# logic.net
KiCad netlist of a schematic drawn in EAGLE
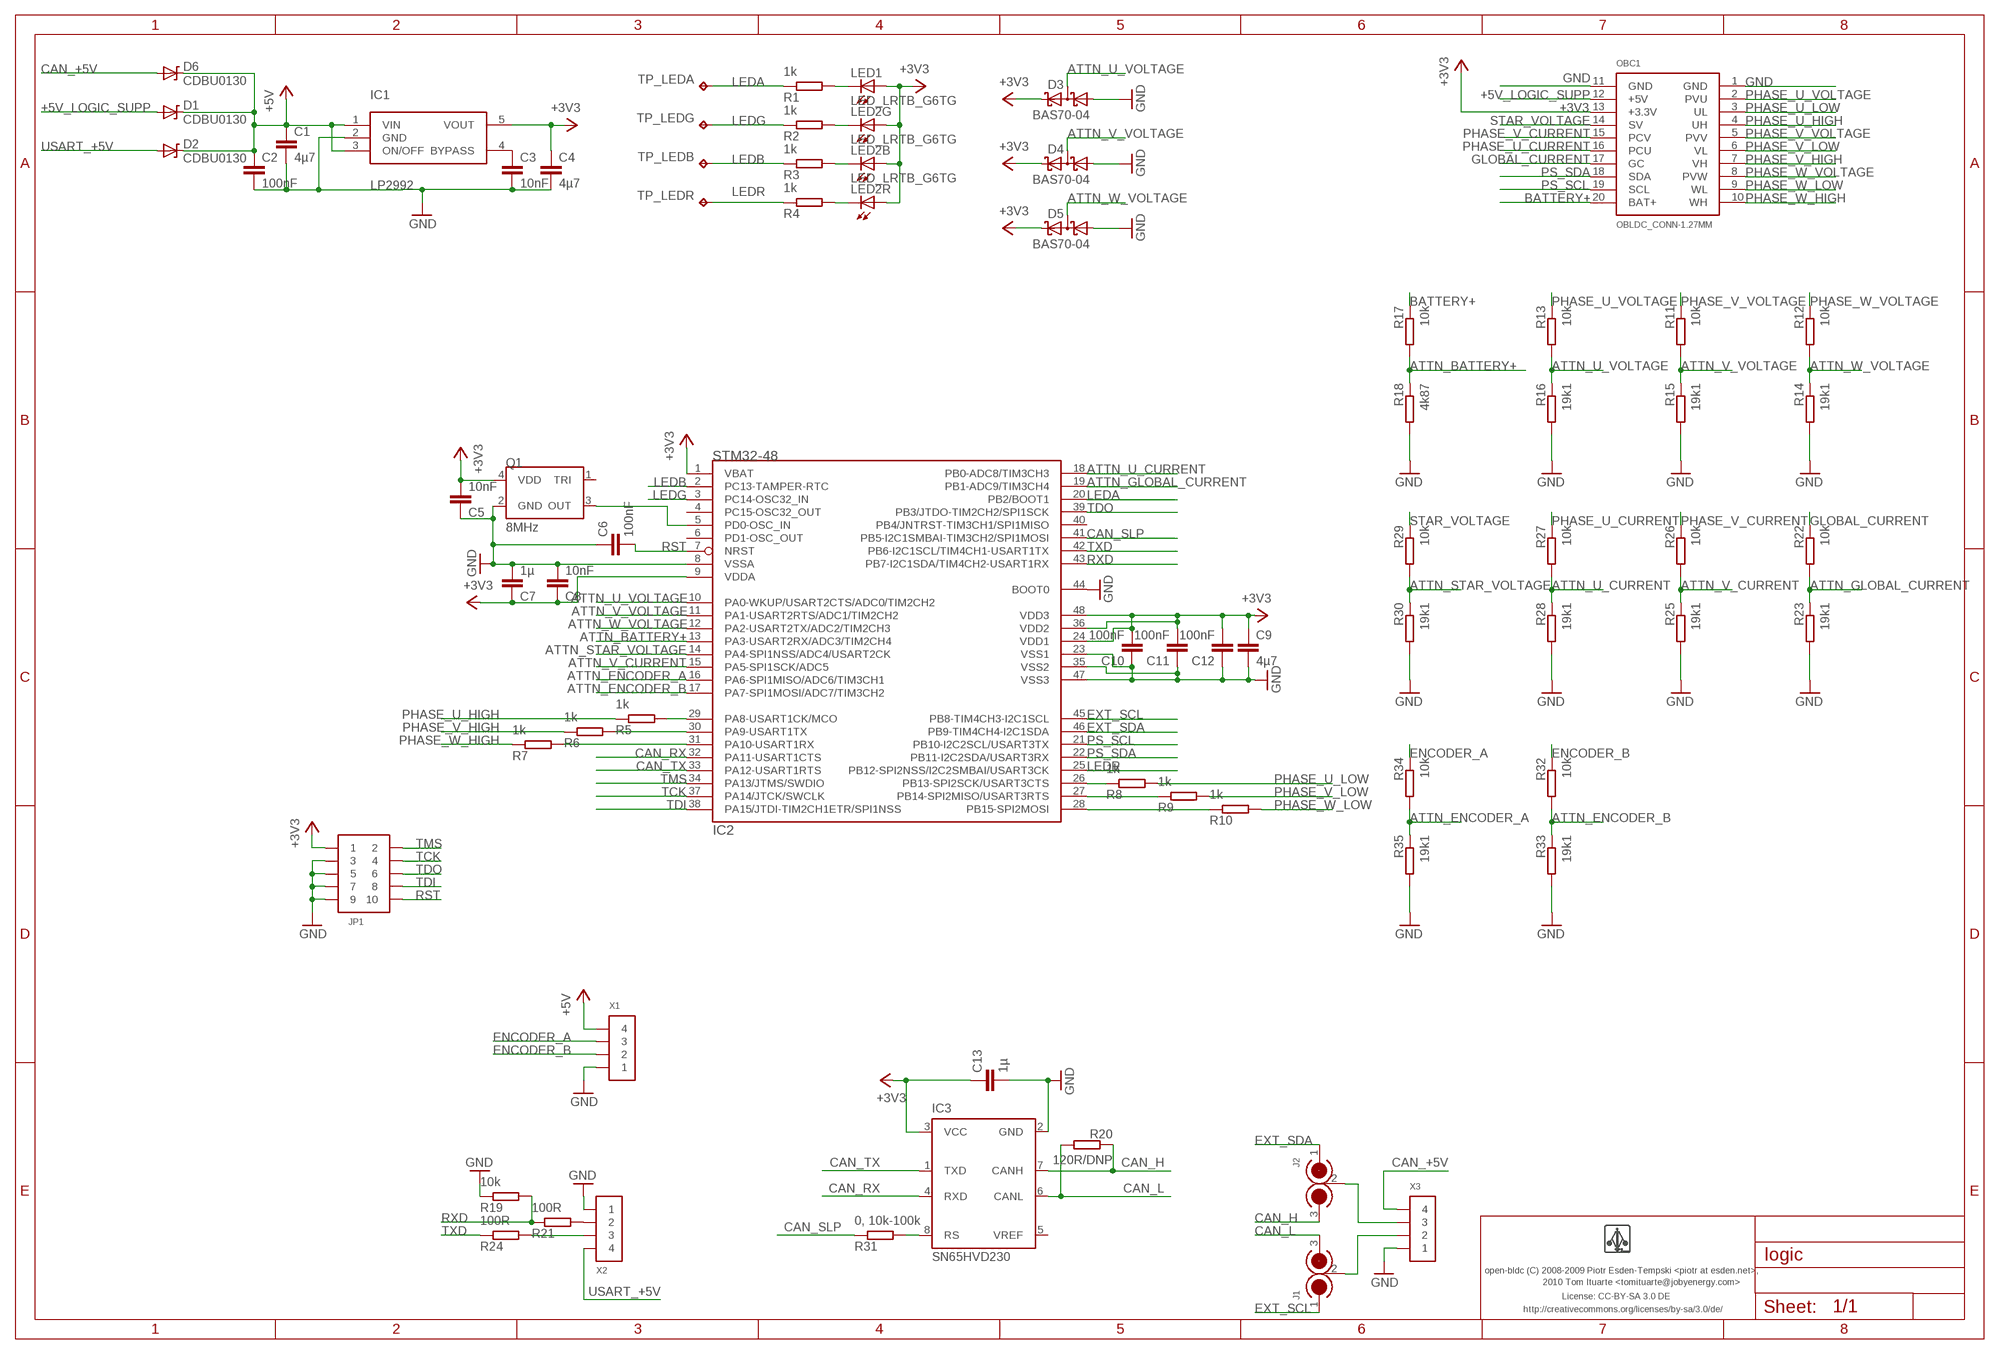
[diagram p0: schematic, sheet 1]

(export (version "E")
  (design (tool "Eeschema 10.0.6"))
  (components
    (comp (ref "C1")
      (value "4µ7")
      (footprint "eagle-import:0603-CAP")
      (libsource (lib "eagle-import") (part "CAPACITOR-0603"))
    )
    (comp (ref "C2")
      (value "100nF")
      (footprint "eagle-import:0603-CAP")
      (libsource (lib "eagle-import") (part "CAPACITOR-0603"))
    )
    (comp (ref "C3")
      (value "10nF")
      (footprint "eagle-import:0603-CAP")
      (libsource (lib "eagle-import") (part "CAPACITOR-0603"))
    )
    (comp (ref "C4")
      (value "4µ7")
      (footprint "eagle-import:0603-CAP")
      (libsource (lib "eagle-import") (part "CAPACITOR-0603"))
    )
    (comp (ref "C5")
      (value "10nF")
      (footprint "eagle-import:0603-CAP")
      (libsource (lib "eagle-import") (part "CAPACITOR-0603"))
    )
    (comp (ref "C6")
      (value "100nF")
      (footprint "eagle-import:0603-CAP")
      (libsource (lib "eagle-import") (part "CAPACITOR-0603"))
    )
    (comp (ref "C7")
      (value "1µ")
      (footprint "eagle-import:0603-CAP")
      (libsource (lib "eagle-import") (part "CAPACITOR-0603"))
    )
    (comp (ref "C8")
      (value "10nF")
      (footprint "eagle-import:0603-CAP")
      (libsource (lib "eagle-import") (part "CAPACITOR-0603"))
    )
    (comp (ref "C9")
      (value "4µ7")
      (footprint "eagle-import:0603-CAP")
      (libsource (lib "eagle-import") (part "CAPACITOR-0603"))
    )
    (comp (ref "C10")
      (value "100nF")
      (footprint "eagle-import:0603-CAP")
      (libsource (lib "eagle-import") (part "CAPACITOR-0603"))
    )
    (comp (ref "C11")
      (value "100nF")
      (footprint "eagle-import:0603-CAP")
      (libsource (lib "eagle-import") (part "CAPACITOR-0603"))
    )
    (comp (ref "C12")
      (value "100nF")
      (footprint "eagle-import:0603-CAP")
      (libsource (lib "eagle-import") (part "CAPACITOR-0603"))
    )
    (comp (ref "C13")
      (value "1µ")
      (footprint "eagle-import:0603-CAP")
      (libsource (lib "eagle-import") (part "CAPACITOR-0603"))
    )
    (comp (ref "D1")
      (value "CDBU0130")
      (footprint "eagle-import:0603-LED")
      (libsource (lib "eagle-import") (part "DIODE-ZENER-0603"))
    )
    (comp (ref "D2")
      (value "CDBU0130")
      (footprint "eagle-import:0603-LED")
      (libsource (lib "eagle-import") (part "DIODE-ZENER-0603"))
    )
    (comp (ref "D3")
      (value "BAS70-04")
      (footprint "eagle-import:SOT23")
      (libsource (lib "eagle-import") (part "BAS70-04"))
    )
    (comp (ref "D4")
      (value "BAS70-04")
      (footprint "eagle-import:SOT23")
      (libsource (lib "eagle-import") (part "BAS70-04"))
    )
    (comp (ref "D5")
      (value "BAS70-04")
      (footprint "eagle-import:SOT23")
      (libsource (lib "eagle-import") (part "BAS70-04"))
    )
    (comp (ref "D6")
      (value "CDBU0130")
      (footprint "eagle-import:0603-LED")
      (libsource (lib "eagle-import") (part "DIODE-ZENER-0603"))
    )
    (comp (ref "IC1")
      (value "LP2992")
      (footprint "eagle-import:SOT23-5")
      (libsource (lib "eagle-import") (part "LP2992"))
    )
    (comp (ref "IC2")
      (value "STM32-48")
      (footprint "eagle-import:LQFP48")
      (libsource (lib "eagle-import") (part "STM32-48"))
    )
    (comp (ref "IC3")
      (value "SN65HVD230")
      (footprint "eagle-import:SO8")
      (libsource (lib "eagle-import") (part "SN65HVD230"))
    )
    (comp (ref "J1")
      (value "CIRC_JMP_2")
      (footprint "eagle-import:CIRC_JMP_2")
      (libsource (lib "eagle-import") (part "CIRC_JMP_2"))
    )
    (comp (ref "J2")
      (value "CIRC_JMP_2")
      (footprint "eagle-import:CIRC_JMP_2")
      (libsource (lib "eagle-import") (part "CIRC_JMP_2"))
    )
    (comp (ref "JP1")
      (value "PIN_HDR_EDG_1.27MM_5-2-DH")
      (footprint "eagle-import:PIN_HDR_1.27MM_SMD_DH_10")
      (libsource (lib "eagle-import") (part "PIN_HDR_EDG_1.27MM_5-2-DH"))
    )
    (comp (ref "LED1")
      (value "AMBER")
      (footprint "eagle-import:0603-LED")
      (libsource (lib "eagle-import") (part "LED-0603"))
    )
    (comp (ref "LED2")
      (value "LED_LRTB_G6TG")
      (footprint "eagle-import:PLCC6")
      (libsource (lib "eagle-import") (part "LED_LRTB_G6TG"))
    )
    (comp (ref "OBC1")
      (value "OBLDC_CONN-1.27MM")
      (footprint "eagle-import:OBLDC_CONN")
      (libsource (lib "eagle-import") (part "OBLDC_CONN-1.27MM"))
    )
    (comp (ref "Q1")
      (value "8MHz")
      (footprint "eagle-import:ASE_OSCILLATOR")
      (libsource (lib "eagle-import") (part "ASE_ASCILLATOR"))
    )
    (comp (ref "R1")
      (value "1k")
      (footprint "eagle-import:0603-RES")
      (libsource (lib "eagle-import") (part "RESISTOR-0603"))
    )
    (comp (ref "R2")
      (value "1k")
      (footprint "eagle-import:0603-RES")
      (libsource (lib "eagle-import") (part "RESISTOR-0603"))
    )
    (comp (ref "R3")
      (value "1k")
      (footprint "eagle-import:0603-RES")
      (libsource (lib "eagle-import") (part "RESISTOR-0603"))
    )
    (comp (ref "R4")
      (value "1k")
      (footprint "eagle-import:0603-RES")
      (libsource (lib "eagle-import") (part "RESISTOR-0603"))
    )
    (comp (ref "R5")
      (value "1k")
      (footprint "eagle-import:0603-RES")
      (libsource (lib "eagle-import") (part "RESISTOR-0603"))
    )
    (comp (ref "R6")
      (value "1k")
      (footprint "eagle-import:0603-RES")
      (libsource (lib "eagle-import") (part "RESISTOR-0603"))
    )
    (comp (ref "R7")
      (value "1k")
      (footprint "eagle-import:0603-RES")
      (libsource (lib "eagle-import") (part "RESISTOR-0603"))
    )
    (comp (ref "R8")
      (value "1k")
      (footprint "eagle-import:0603-RES")
      (libsource (lib "eagle-import") (part "RESISTOR-0603"))
    )
    (comp (ref "R9")
      (value "1k")
      (footprint "eagle-import:0603-RES")
      (libsource (lib "eagle-import") (part "RESISTOR-0603"))
    )
    (comp (ref "R10")
      (value "1k")
      (footprint "eagle-import:0603-RES")
      (libsource (lib "eagle-import") (part "RESISTOR-0603"))
    )
    (comp (ref "R11")
      (value "10k")
      (footprint "eagle-import:0603-RES")
      (libsource (lib "eagle-import") (part "RESISTOR-0603"))
    )
    (comp (ref "R12")
      (value "10k")
      (footprint "eagle-import:0603-RES")
      (libsource (lib "eagle-import") (part "RESISTOR-0603"))
    )
    (comp (ref "R13")
      (value "10k")
      (footprint "eagle-import:0603-RES")
      (libsource (lib "eagle-import") (part "RESISTOR-0603"))
    )
    (comp (ref "R14")
      (value "19k1")
      (footprint "eagle-import:0603-RES")
      (libsource (lib "eagle-import") (part "RESISTOR-0603"))
    )
    (comp (ref "R15")
      (value "19k1")
      (footprint "eagle-import:0603-RES")
      (libsource (lib "eagle-import") (part "RESISTOR-0603"))
    )
    (comp (ref "R16")
      (value "19k1")
      (footprint "eagle-import:0603-RES")
      (libsource (lib "eagle-import") (part "RESISTOR-0603"))
    )
    (comp (ref "R17")
      (value "10k")
      (footprint "eagle-import:0603-RES")
      (libsource (lib "eagle-import") (part "RESISTOR-0603"))
    )
    (comp (ref "R18")
      (value "4k87")
      (footprint "eagle-import:0603-RES")
      (libsource (lib "eagle-import") (part "RESISTOR-0603"))
    )
    (comp (ref "R19")
      (value "10k")
      (footprint "eagle-import:0603-RES")
      (libsource (lib "eagle-import") (part "RESISTOR-0603"))
    )
    (comp (ref "R20")
      (value "120R/DNP")
      (footprint "eagle-import:0603-RES")
      (libsource (lib "eagle-import") (part "RESISTOR-0603"))
    )
    (comp (ref "R21")
      (value "100R")
      (footprint "eagle-import:0603-RES")
      (libsource (lib "eagle-import") (part "RESISTOR-0603"))
    )
    (comp (ref "R22")
      (value "10k")
      (footprint "eagle-import:0603-RES")
      (libsource (lib "eagle-import") (part "RESISTOR-0603"))
    )
    (comp (ref "R23")
      (value "19k1")
      (footprint "eagle-import:0603-RES")
      (libsource (lib "eagle-import") (part "RESISTOR-0603"))
    )
    (comp (ref "R24")
      (value "100R")
      (footprint "eagle-import:0603-RES")
      (libsource (lib "eagle-import") (part "RESISTOR-0603"))
    )
    (comp (ref "R25")
      (value "19k1")
      (footprint "eagle-import:0603-RES")
      (libsource (lib "eagle-import") (part "RESISTOR-0603"))
    )
    (comp (ref "R26")
      (value "10k")
      (footprint "eagle-import:0603-RES")
      (libsource (lib "eagle-import") (part "RESISTOR-0603"))
    )
    (comp (ref "R27")
      (value "10k")
      (footprint "eagle-import:0603-RES")
      (libsource (lib "eagle-import") (part "RESISTOR-0603"))
    )
    (comp (ref "R28")
      (value "19k1")
      (footprint "eagle-import:0603-RES")
      (libsource (lib "eagle-import") (part "RESISTOR-0603"))
    )
    (comp (ref "R29")
      (value "10k")
      (footprint "eagle-import:0603-RES")
      (libsource (lib "eagle-import") (part "RESISTOR-0603"))
    )
    (comp (ref "R30")
      (value "19k1")
      (footprint "eagle-import:0603-RES")
      (libsource (lib "eagle-import") (part "RESISTOR-0603"))
    )
    (comp (ref "R31")
      (value "0, 10k-100k")
      (footprint "eagle-import:0603-RES")
      (libsource (lib "eagle-import") (part "RESISTOR-0603"))
    )
    (comp (ref "R32")
      (value "10k")
      (footprint "eagle-import:0603-RES")
      (libsource (lib "eagle-import") (part "RESISTOR-0603"))
    )
    (comp (ref "R33")
      (value "19k1")
      (footprint "eagle-import:0603-RES")
      (libsource (lib "eagle-import") (part "RESISTOR-0603"))
    )
    (comp (ref "R34")
      (value "10k")
      (footprint "eagle-import:0603-RES")
      (libsource (lib "eagle-import") (part "RESISTOR-0603"))
    )
    (comp (ref "R35")
      (value "19k1")
      (footprint "eagle-import:0603-RES")
      (libsource (lib "eagle-import") (part "RESISTOR-0603"))
    )
    (comp (ref "TP_LEDA")
      (value "TP-SMD")
      (footprint "eagle-import:MINI_TESTPAD")
      (libsource (lib "eagle-import") (part "TP-SMD"))
    )
    (comp (ref "TP_LEDB")
      (value "TP-SMD")
      (footprint "eagle-import:MINI_TESTPAD")
      (libsource (lib "eagle-import") (part "TP-SMD"))
    )
    (comp (ref "TP_LEDG")
      (value "TP-SMD")
      (footprint "eagle-import:MINI_TESTPAD")
      (libsource (lib "eagle-import") (part "TP-SMD"))
    )
    (comp (ref "TP_LEDR")
      (value "TP-SMD")
      (footprint "eagle-import:MINI_TESTPAD")
      (libsource (lib "eagle-import") (part "TP-SMD"))
    )
    (comp (ref "U$1")
      (value "LOGO")
      (footprint "eagle-import:LOGO")
      (libsource (lib "eagle-import") (part "LOGO-NORM"))
    )
    (comp (ref "X1")
      (value "CONN_4-1-53261")
      (footprint "eagle-import:PB-53261-04")
      (libsource (lib "eagle-import") (part "CONN_4-1-53261"))
    )
    (comp (ref "X2")
      (value "CONN_4-1-53261")
      (footprint "eagle-import:PB-53261-04")
      (libsource (lib "eagle-import") (part "CONN_4-1-53261"))
    )
    (comp (ref "X3")
      (value "CONN_4-1-53261")
      (footprint "eagle-import:PB-53261-04")
      (libsource (lib "eagle-import") (part "CONN_4-1-53261"))
    )
  )
  (nets
    (net (code "1") (name "+3V3") (class "Default")
      (node (ref "C10") (pin "P$2") (pinfunction "2_P$2") (pintype "passive"))
      (node (ref "C11") (pin "P$2") (pinfunction "2_P$2") (pintype "passive"))
      (node (ref "C12") (pin "P$2") (pinfunction "2_P$2") (pintype "passive"))
      (node (ref "C13") (pin "P$1") (pinfunction "1_P$1") (pintype "passive"))
      (node (ref "C4") (pin "P$1") (pinfunction "1_P$1") (pintype "passive"))
      (node (ref "C5") (pin "P$2") (pinfunction "2_P$2") (pintype "passive"))
      (node (ref "C7") (pin "P$1") (pinfunction "1_P$1") (pintype "passive"))
      (node (ref "C8") (pin "P$1") (pinfunction "1_P$1") (pintype "passive"))
      (node (ref "C9") (pin "P$1") (pinfunction "1_P$1") (pintype "passive"))
      (node (ref "D3") (pin "2") (pinfunction "C2_2") (pintype "passive"))
      (node (ref "D4") (pin "2") (pinfunction "C2_2") (pintype "passive"))
      (node (ref "D5") (pin "2") (pinfunction "C2_2") (pintype "passive"))
      (node (ref "IC1") (pin "5") (pinfunction "VOUT_5") (pintype "bidirectional"))
      (node (ref "IC2") (pin "1") (pinfunction "VBAT_1") (pintype "power_in"))
      (node (ref "IC2") (pin "24") (pinfunction "VDD1_24") (pintype "power_in"))
      (node (ref "IC2") (pin "36") (pinfunction "VDD2_36") (pintype "power_in"))
      (node (ref "IC2") (pin "48") (pinfunction "VDD3_48") (pintype "power_in"))
      (node (ref "IC2") (pin "9") (pinfunction "VDDA_9") (pintype "power_in"))
      (node (ref "IC3") (pin "3") (pinfunction "VCC_3") (pintype "power_in"))
      (node (ref "JP1") (pin "1") (pinfunction "1_1") (pintype "bidirectional"))
      (node (ref "LED1") (pin "A") (pinfunction "A_A") (pintype "passive"))
      (node (ref "LED2") (pin "A1") (pinfunction "A_A1") (pintype "passive"))
      (node (ref "LED2") (pin "A2") (pinfunction "A_A2") (pintype "passive"))
      (node (ref "LED2") (pin "A3") (pinfunction "A_A3") (pintype "passive"))
      (node (ref "OBC1") (pin "13") (pinfunction "+3.3V_13") (pintype "bidirectional"))
      (node (ref "Q1") (pin "4") (pinfunction "VDD_4") (pintype "power_in"))
    )
    (net (code "2") (name "+5V") (class "Default")
      (node (ref "C1") (pin "P$1") (pinfunction "1_P$1") (pintype "passive"))
      (node (ref "C2") (pin "P$1") (pinfunction "1_P$1") (pintype "passive"))
      (node (ref "D1") (pin "C") (pinfunction "C_C") (pintype "passive"))
      (node (ref "D2") (pin "C") (pinfunction "C_C") (pintype "passive"))
      (node (ref "D6") (pin "C") (pinfunction "C_C") (pintype "passive"))
      (node (ref "IC1") (pin "1") (pinfunction "VIN_1") (pintype "bidirectional"))
      (node (ref "IC1") (pin "3") (pinfunction "ON/OFF_3") (pintype "bidirectional"))
      (node (ref "X1") (pin "4") (pinfunction "4_4") (pintype "bidirectional"))
    )
    (net (code "3") (name "/+5V_LOGIC_SUPP") (class "Default")
      (node (ref "D1") (pin "A") (pinfunction "A_A") (pintype "passive"))
      (node (ref "OBC1") (pin "12") (pinfunction "+5V_12") (pintype "bidirectional"))
    )
    (net (code "4") (name "/ATTN_BATTERY+") (class "Default")
      (node (ref "IC2") (pin "13") (pinfunction "PA3-USART2RX/ADC3/TIM2CH4_13") (pintype "bidirectional"))
      (node (ref "R17") (pin "P$2") (pinfunction "2_P$2") (pintype "passive"))
      (node (ref "R18") (pin "P$1") (pinfunction "1_P$1") (pintype "passive"))
    )
    (net (code "5") (name "/ATTN_ENCODER_A") (class "Default")
      (node (ref "IC2") (pin "16") (pinfunction "PA6-SPI1MISO/ADC6/TIM3CH1_16") (pintype "bidirectional"))
      (node (ref "R34") (pin "P$2") (pinfunction "2_P$2") (pintype "passive"))
      (node (ref "R35") (pin "P$1") (pinfunction "1_P$1") (pintype "passive"))
    )
    (net (code "6") (name "/ATTN_ENCODER_B") (class "Default")
      (node (ref "IC2") (pin "17") (pinfunction "PA7-SPI1MOSI/ADC7/TIM3CH2_17") (pintype "bidirectional"))
      (node (ref "R32") (pin "P$2") (pinfunction "2_P$2") (pintype "passive"))
      (node (ref "R33") (pin "P$1") (pinfunction "1_P$1") (pintype "passive"))
    )
    (net (code "7") (name "/ATTN_GLOBAL_CURRENT") (class "Default")
      (node (ref "IC2") (pin "19") (pinfunction "PB1-ADC9/TIM3CH4_19") (pintype "bidirectional"))
      (node (ref "R22") (pin "P$2") (pinfunction "2_P$2") (pintype "passive"))
      (node (ref "R23") (pin "P$1") (pinfunction "1_P$1") (pintype "passive"))
    )
    (net (code "8") (name "/ATTN_STAR_VOLTAGE") (class "Default")
      (node (ref "IC2") (pin "14") (pinfunction "PA4-SPI1NSS/ADC4/USART2CK_14") (pintype "bidirectional"))
      (node (ref "R29") (pin "P$2") (pinfunction "2_P$2") (pintype "passive"))
      (node (ref "R30") (pin "P$1") (pinfunction "1_P$1") (pintype "passive"))
    )
    (net (code "9") (name "/ATTN_U_CURRENT") (class "Default")
      (node (ref "IC2") (pin "18") (pinfunction "PB0-ADC8/TIM3CH3_18") (pintype "bidirectional"))
      (node (ref "R27") (pin "P$2") (pinfunction "2_P$2") (pintype "passive"))
      (node (ref "R28") (pin "P$1") (pinfunction "1_P$1") (pintype "passive"))
    )
    (net (code "10") (name "/ATTN_U_VOLTAGE") (class "Default")
      (node (ref "D3") (pin "3") (pinfunction "C1A2_3") (pintype "passive"))
      (node (ref "IC2") (pin "10") (pinfunction "PA0-WKUP/USART2CTS/ADC0/TIM2CH2_10") (pintype "bidirectional"))
      (node (ref "R13") (pin "P$2") (pinfunction "2_P$2") (pintype "passive"))
      (node (ref "R16") (pin "P$1") (pinfunction "1_P$1") (pintype "passive"))
    )
    (net (code "11") (name "/ATTN_V_CURRENT") (class "Default")
      (node (ref "IC2") (pin "15") (pinfunction "PA5-SPI1SCK/ADC5_15") (pintype "bidirectional"))
      (node (ref "R25") (pin "P$1") (pinfunction "1_P$1") (pintype "passive"))
      (node (ref "R26") (pin "P$2") (pinfunction "2_P$2") (pintype "passive"))
    )
    (net (code "12") (name "/ATTN_V_VOLTAGE") (class "Default")
      (node (ref "D4") (pin "3") (pinfunction "C1A2_3") (pintype "passive"))
      (node (ref "IC2") (pin "11") (pinfunction "PA1-USART2RTS/ADC1/TIM2CH2_11") (pintype "bidirectional"))
      (node (ref "R11") (pin "P$2") (pinfunction "2_P$2") (pintype "passive"))
      (node (ref "R15") (pin "P$1") (pinfunction "1_P$1") (pintype "passive"))
    )
    (net (code "13") (name "/ATTN_W_VOLTAGE") (class "Default")
      (node (ref "D5") (pin "3") (pinfunction "C1A2_3") (pintype "passive"))
      (node (ref "IC2") (pin "12") (pinfunction "PA2-USART2TX/ADC2/TIM2CH3_12") (pintype "bidirectional"))
      (node (ref "R12") (pin "P$2") (pinfunction "2_P$2") (pintype "passive"))
      (node (ref "R14") (pin "P$1") (pinfunction "1_P$1") (pintype "passive"))
    )
    (net (code "14") (name "/BATTERY+") (class "Default")
      (node (ref "OBC1") (pin "20") (pinfunction "BAT+_20") (pintype "bidirectional"))
      (node (ref "R17") (pin "P$1") (pinfunction "1_P$1") (pintype "passive"))
    )
    (net (code "15") (name "/CAN_+5V") (class "Default")
      (node (ref "D6") (pin "A") (pinfunction "A_A") (pintype "passive"))
      (node (ref "X3") (pin "4") (pinfunction "4_4") (pintype "bidirectional"))
    )
    (net (code "16") (name "/CAN_H") (class "Default")
      (node (ref "IC3") (pin "7") (pinfunction "CANH_7") (pintype "bidirectional"))
      (node (ref "J2") (pin "3") (pinfunction "P$3_3") (pintype "bidirectional"))
      (node (ref "R20") (pin "P$1") (pinfunction "1_P$1") (pintype "passive"))
    )
    (net (code "17") (name "/CAN_L") (class "Default")
      (node (ref "IC3") (pin "6") (pinfunction "CANL_6") (pintype "bidirectional"))
      (node (ref "J1") (pin "3") (pinfunction "P$3_3") (pintype "bidirectional"))
      (node (ref "R20") (pin "P$2") (pinfunction "2_P$2") (pintype "passive"))
    )
    (net (code "18") (name "/CAN_RX") (class "Default")
      (node (ref "IC2") (pin "32") (pinfunction "PA11-USART1CTS_32") (pintype "bidirectional"))
      (node (ref "IC3") (pin "4") (pinfunction "RXD_4") (pintype "output"))
    )
    (net (code "19") (name "/CAN_SLP") (class "Default")
      (node (ref "IC2") (pin "41") (pinfunction "PB5-I2C1SMBAI-TIM3CH2/SPI1MOSI_41") (pintype "bidirectional"))
      (node (ref "R31") (pin "P$1") (pinfunction "1_P$1") (pintype "passive"))
    )
    (net (code "20") (name "/CAN_TX") (class "Default")
      (node (ref "IC2") (pin "33") (pinfunction "PA12-USART1RTS_33") (pintype "bidirectional"))
      (node (ref "IC3") (pin "1") (pinfunction "TXD_1") (pintype "input"))
    )
    (net (code "21") (name "/ENCODER_A") (class "Default")
      (node (ref "R34") (pin "P$1") (pinfunction "1_P$1") (pintype "passive"))
      (node (ref "X1") (pin "3") (pinfunction "3_3") (pintype "bidirectional"))
    )
    (net (code "22") (name "/ENCODER_B") (class "Default")
      (node (ref "R32") (pin "P$1") (pinfunction "1_P$1") (pintype "passive"))
      (node (ref "X1") (pin "2") (pinfunction "2_2") (pintype "bidirectional"))
    )
    (net (code "23") (name "/EXT_SCL") (class "Default")
      (node (ref "IC2") (pin "45") (pinfunction "PB8-TIM4CH3-I2C1SCL_45") (pintype "bidirectional"))
      (node (ref "J1") (pin "1") (pinfunction "P$1_1") (pintype "bidirectional"))
    )
    (net (code "24") (name "/EXT_SDA") (class "Default")
      (node (ref "IC2") (pin "46") (pinfunction "PB9-TIM4CH4-I2C1SDA_46") (pintype "bidirectional"))
      (node (ref "J2") (pin "1") (pinfunction "P$1_1") (pintype "bidirectional"))
    )
    (net (code "25") (name "/GLOBAL_CURRENT") (class "Default")
      (node (ref "OBC1") (pin "17") (pinfunction "GC_17") (pintype "bidirectional"))
      (node (ref "R22") (pin "P$1") (pinfunction "1_P$1") (pintype "passive"))
    )
    (net (code "26") (name "/LEDA") (class "Default")
      (node (ref "IC2") (pin "20") (pinfunction "PB2/BOOT1_20") (pintype "bidirectional"))
      (node (ref "R1") (pin "P$1") (pinfunction "1_P$1") (pintype "passive"))
      (node (ref "TP_LEDA") (pin "1") (pinfunction "TP_1") (pintype "input"))
    )
    (net (code "27") (name "/LEDB") (class "Default")
      (node (ref "IC2") (pin "2") (pinfunction "PC13-TAMPER-RTC_2") (pintype "bidirectional"))
      (node (ref "R3") (pin "P$1") (pinfunction "1_P$1") (pintype "passive"))
      (node (ref "TP_LEDB") (pin "1") (pinfunction "TP_1") (pintype "input"))
    )
    (net (code "28") (name "/LEDG") (class "Default")
      (node (ref "IC2") (pin "3") (pinfunction "PC14-OSC32_IN_3") (pintype "bidirectional"))
      (node (ref "R2") (pin "P$1") (pinfunction "1_P$1") (pintype "passive"))
      (node (ref "TP_LEDG") (pin "1") (pinfunction "TP_1") (pintype "input"))
    )
    (net (code "29") (name "/LEDR") (class "Default")
      (node (ref "IC2") (pin "25") (pinfunction "PB12-SPI2NSS/I2C2SMBAI/USART3CK_25") (pintype "bidirectional"))
      (node (ref "R4") (pin "P$1") (pinfunction "1_P$1") (pintype "passive"))
      (node (ref "TP_LEDR") (pin "1") (pinfunction "TP_1") (pintype "input"))
    )
    (net (code "30") (name "/PHASE_U_CURRENT") (class "Default")
      (node (ref "OBC1") (pin "16") (pinfunction "PCU_16") (pintype "bidirectional"))
      (node (ref "R27") (pin "P$1") (pinfunction "1_P$1") (pintype "passive"))
    )
    (net (code "31") (name "/PHASE_U_HIGH") (class "Default")
      (node (ref "OBC1") (pin "4") (pinfunction "UH_4") (pintype "bidirectional"))
      (node (ref "R5") (pin "P$1") (pinfunction "1_P$1") (pintype "passive"))
    )
    (net (code "32") (name "/PHASE_U_LOW") (class "Default")
      (node (ref "OBC1") (pin "3") (pinfunction "UL_3") (pintype "bidirectional"))
      (node (ref "R8") (pin "P$2") (pinfunction "2_P$2") (pintype "passive"))
    )
    (net (code "33") (name "/PHASE_U_VOLTAGE") (class "Default")
      (node (ref "OBC1") (pin "2") (pinfunction "PVU_2") (pintype "bidirectional"))
      (node (ref "R13") (pin "P$1") (pinfunction "1_P$1") (pintype "passive"))
    )
    (net (code "34") (name "/PHASE_V_CURRENT") (class "Default")
      (node (ref "OBC1") (pin "15") (pinfunction "PCV_15") (pintype "bidirectional"))
      (node (ref "R26") (pin "P$1") (pinfunction "1_P$1") (pintype "passive"))
    )
    (net (code "35") (name "/PHASE_V_HIGH") (class "Default")
      (node (ref "OBC1") (pin "7") (pinfunction "VH_7") (pintype "bidirectional"))
      (node (ref "R6") (pin "P$1") (pinfunction "1_P$1") (pintype "passive"))
    )
    (net (code "36") (name "/PHASE_V_LOW") (class "Default")
      (node (ref "OBC1") (pin "6") (pinfunction "VL_6") (pintype "bidirectional"))
      (node (ref "R9") (pin "P$2") (pinfunction "2_P$2") (pintype "passive"))
    )
    (net (code "37") (name "/PHASE_V_VOLTAGE") (class "Default")
      (node (ref "OBC1") (pin "5") (pinfunction "PVV_5") (pintype "bidirectional"))
      (node (ref "R11") (pin "P$1") (pinfunction "1_P$1") (pintype "passive"))
    )
    (net (code "38") (name "/PHASE_W_HIGH") (class "Default")
      (node (ref "OBC1") (pin "10") (pinfunction "WH_10") (pintype "bidirectional"))
      (node (ref "R7") (pin "P$1") (pinfunction "1_P$1") (pintype "passive"))
    )
    (net (code "39") (name "/PHASE_W_LOW") (class "Default")
      (node (ref "OBC1") (pin "9") (pinfunction "WL_9") (pintype "bidirectional"))
      (node (ref "R10") (pin "P$2") (pinfunction "2_P$2") (pintype "passive"))
    )
    (net (code "40") (name "/PHASE_W_VOLTAGE") (class "Default")
      (node (ref "OBC1") (pin "8") (pinfunction "PVW_8") (pintype "bidirectional"))
      (node (ref "R12") (pin "P$1") (pinfunction "1_P$1") (pintype "passive"))
    )
    (net (code "41") (name "/PS_SCL") (class "Default")
      (node (ref "IC2") (pin "21") (pinfunction "PB10-I2C2SCL/USART3TX_21") (pintype "bidirectional"))
      (node (ref "OBC1") (pin "19") (pinfunction "SCL_19") (pintype "bidirectional"))
    )
    (net (code "42") (name "/PS_SDA") (class "Default")
      (node (ref "IC2") (pin "22") (pinfunction "PB11-I2C2SDA/USART3RX_22") (pintype "bidirectional"))
      (node (ref "OBC1") (pin "18") (pinfunction "SDA_18") (pintype "bidirectional"))
    )
    (net (code "43") (name "/RST") (class "Default")
      (node (ref "C6") (pin "P$2") (pinfunction "2_P$2") (pintype "passive"))
      (node (ref "IC2") (pin "7") (pinfunction "NRST_7") (pintype "bidirectional"))
      (node (ref "JP1") (pin "10") (pinfunction "10_10") (pintype "bidirectional"))
    )
    (net (code "44") (name "/RXD") (class "Default")
      (node (ref "IC2") (pin "43") (pinfunction "PB7-I2C1SDA/TIM4CH2-USART1RX_43") (pintype "bidirectional"))
      (node (ref "R19") (pin "P$2") (pinfunction "2_P$2") (pintype "passive"))
      (node (ref "R21") (pin "P$1") (pinfunction "1_P$1") (pintype "passive"))
    )
    (net (code "45") (name "/STAR_VOLTAGE") (class "Default")
      (node (ref "OBC1") (pin "14") (pinfunction "SV_14") (pintype "bidirectional"))
      (node (ref "R29") (pin "P$1") (pinfunction "1_P$1") (pintype "passive"))
    )
    (net (code "46") (name "/TCK") (class "Default")
      (node (ref "IC2") (pin "37") (pinfunction "PA14/JTCK/SWCLK_37") (pintype "bidirectional"))
      (node (ref "JP1") (pin "4") (pinfunction "4_4") (pintype "bidirectional"))
    )
    (net (code "47") (name "/TDI") (class "Default")
      (node (ref "IC2") (pin "38") (pinfunction "PA15/JTDI-TIM2CH1ETR/SPI1NSS_38") (pintype "bidirectional"))
      (node (ref "JP1") (pin "8") (pinfunction "8_8") (pintype "bidirectional"))
    )
    (net (code "48") (name "/TDO") (class "Default")
      (node (ref "IC2") (pin "39") (pinfunction "PB3/JTDO-TIM2CH2/SPI1SCK_39") (pintype "bidirectional"))
      (node (ref "JP1") (pin "6") (pinfunction "6_6") (pintype "bidirectional"))
    )
    (net (code "49") (name "/TMS") (class "Default")
      (node (ref "IC2") (pin "34") (pinfunction "PA13/JTMS/SWDIO_34") (pintype "bidirectional"))
      (node (ref "JP1") (pin "2") (pinfunction "2_2") (pintype "bidirectional"))
    )
    (net (code "50") (name "/TXD") (class "Default")
      (node (ref "IC2") (pin "42") (pinfunction "PB6-I2C1SCL/TIM4CH1-USART1TX_42") (pintype "bidirectional"))
      (node (ref "R24") (pin "P$1") (pinfunction "1_P$1") (pintype "passive"))
    )
    (net (code "51") (name "/USART_+5V") (class "Default")
      (node (ref "D2") (pin "A") (pinfunction "A_A") (pintype "passive"))
      (node (ref "X2") (pin "4") (pinfunction "4_4") (pintype "bidirectional"))
    )
    (net (code "52") (name "GND") (class "Default")
      (node (ref "C1") (pin "P$2") (pinfunction "2_P$2") (pintype "passive"))
      (node (ref "C10") (pin "P$1") (pinfunction "1_P$1") (pintype "passive"))
      (node (ref "C11") (pin "P$1") (pinfunction "1_P$1") (pintype "passive"))
      (node (ref "C12") (pin "P$1") (pinfunction "1_P$1") (pintype "passive"))
      (node (ref "C13") (pin "P$2") (pinfunction "2_P$2") (pintype "passive"))
      (node (ref "C2") (pin "P$2") (pinfunction "2_P$2") (pintype "passive"))
      (node (ref "C3") (pin "P$2") (pinfunction "2_P$2") (pintype "passive"))
      (node (ref "C4") (pin "P$2") (pinfunction "2_P$2") (pintype "passive"))
      (node (ref "C5") (pin "P$1") (pinfunction "1_P$1") (pintype "passive"))
      (node (ref "C6") (pin "P$1") (pinfunction "1_P$1") (pintype "passive"))
      (node (ref "C7") (pin "P$2") (pinfunction "2_P$2") (pintype "passive"))
      (node (ref "C8") (pin "P$2") (pinfunction "2_P$2") (pintype "passive"))
      (node (ref "C9") (pin "P$2") (pinfunction "2_P$2") (pintype "passive"))
      (node (ref "D3") (pin "1") (pinfunction "A1_1") (pintype "passive"))
      (node (ref "D4") (pin "1") (pinfunction "A1_1") (pintype "passive"))
      (node (ref "D5") (pin "1") (pinfunction "A1_1") (pintype "passive"))
      (node (ref "IC1") (pin "2") (pinfunction "GND_2") (pintype "bidirectional"))
      (node (ref "IC2") (pin "23") (pinfunction "VSS1_23") (pintype "power_in"))
      (node (ref "IC2") (pin "35") (pinfunction "VSS2_35") (pintype "power_in"))
      (node (ref "IC2") (pin "44") (pinfunction "BOOT0_44") (pintype "input"))
      (node (ref "IC2") (pin "47") (pinfunction "VSS3_47") (pintype "power_in"))
      (node (ref "IC2") (pin "8") (pinfunction "VSSA_8") (pintype "power_in"))
      (node (ref "IC3") (pin "2") (pinfunction "GND_2") (pintype "power_in"))
      (node (ref "JP1") (pin "3") (pinfunction "3_3") (pintype "bidirectional"))
      (node (ref "JP1") (pin "5") (pinfunction "5_5") (pintype "bidirectional"))
      (node (ref "JP1") (pin "7") (pinfunction "7_7") (pintype "bidirectional"))
      (node (ref "JP1") (pin "9") (pinfunction "9_9") (pintype "bidirectional"))
      (node (ref "OBC1") (pin "1") (pinfunction "GND_1") (pintype "bidirectional"))
      (node (ref "OBC1") (pin "11") (pinfunction "GND_11") (pintype "bidirectional"))
      (node (ref "Q1") (pin "2") (pinfunction "GND_2") (pintype "power_in"))
      (node (ref "R14") (pin "P$2") (pinfunction "2_P$2") (pintype "passive"))
      (node (ref "R15") (pin "P$2") (pinfunction "2_P$2") (pintype "passive"))
      (node (ref "R16") (pin "P$2") (pinfunction "2_P$2") (pintype "passive"))
      (node (ref "R18") (pin "P$2") (pinfunction "2_P$2") (pintype "passive"))
      (node (ref "R19") (pin "P$1") (pinfunction "1_P$1") (pintype "passive"))
      (node (ref "R23") (pin "P$2") (pinfunction "2_P$2") (pintype "passive"))
      (node (ref "R25") (pin "P$2") (pinfunction "2_P$2") (pintype "passive"))
      (node (ref "R28") (pin "P$2") (pinfunction "2_P$2") (pintype "passive"))
      (node (ref "R30") (pin "P$2") (pinfunction "2_P$2") (pintype "passive"))
      (node (ref "R33") (pin "P$2") (pinfunction "2_P$2") (pintype "passive"))
      (node (ref "R35") (pin "P$2") (pinfunction "2_P$2") (pintype "passive"))
      (node (ref "X1") (pin "1") (pinfunction "1_1") (pintype "bidirectional"))
      (node (ref "X2") (pin "1") (pinfunction "1_1") (pintype "bidirectional"))
      (node (ref "X3") (pin "1") (pinfunction "1_1") (pintype "bidirectional"))
    )
    (net (code "53") (name "Net-(C3-1)") (class "Default")
      (node (ref "C3") (pin "P$1") (pinfunction "1_P$1") (pintype "passive"))
      (node (ref "IC1") (pin "4") (pinfunction "BYPASS_4") (pintype "bidirectional"))
    )
    (net (code "54") (name "Net-(IC2-PA8-USART1CK{slash}MCO)") (class "Default")
      (node (ref "IC2") (pin "29") (pinfunction "PA8-USART1CK/MCO_29") (pintype "bidirectional"))
      (node (ref "R5") (pin "P$2") (pinfunction "2_P$2") (pintype "passive"))
    )
    (net (code "55") (name "Net-(IC2-PA9-USART1TX)") (class "Default")
      (node (ref "IC2") (pin "30") (pinfunction "PA9-USART1TX_30") (pintype "bidirectional"))
      (node (ref "R6") (pin "P$2") (pinfunction "2_P$2") (pintype "passive"))
    )
    (net (code "56") (name "Net-(IC2-PA10-USART1RX)") (class "Default")
      (node (ref "IC2") (pin "31") (pinfunction "PA10-USART1RX_31") (pintype "bidirectional"))
      (node (ref "R7") (pin "P$2") (pinfunction "2_P$2") (pintype "passive"))
    )
    (net (code "57") (name "Net-(IC2-PB13-SPI2SCK{slash}USART3CTS)") (class "Default")
      (node (ref "IC2") (pin "26") (pinfunction "PB13-SPI2SCK/USART3CTS_26") (pintype "bidirectional"))
      (node (ref "R8") (pin "P$1") (pinfunction "1_P$1") (pintype "passive"))
    )
    (net (code "58") (name "Net-(IC2-PB14-SPI2MISO{slash}USART3RTS)") (class "Default")
      (node (ref "IC2") (pin "27") (pinfunction "PB14-SPI2MISO/USART3RTS_27") (pintype "bidirectional"))
      (node (ref "R9") (pin "P$1") (pinfunction "1_P$1") (pintype "passive"))
    )
    (net (code "59") (name "Net-(IC2-PB15-SPI2MOSI)") (class "Default")
      (node (ref "IC2") (pin "28") (pinfunction "PB15-SPI2MOSI_28") (pintype "bidirectional"))
      (node (ref "R10") (pin "P$1") (pinfunction "1_P$1") (pintype "passive"))
    )
    (net (code "60") (name "Net-(IC2-PD0-OSC_IN)") (class "Default")
      (node (ref "IC2") (pin "5") (pinfunction "PD0-OSC_IN_5") (pintype "input"))
      (node (ref "Q1") (pin "3") (pinfunction "OUT_3") (pintype "output"))
    )
    (net (code "61") (name "Net-(IC3-RS)") (class "Default")
      (node (ref "IC3") (pin "8") (pinfunction "RS_8") (pintype "input"))
      (node (ref "R31") (pin "P$2") (pinfunction "2_P$2") (pintype "passive"))
    )
    (net (code "62") (name "Net-(J1-P$2)") (class "Default")
      (node (ref "J1") (pin "2") (pinfunction "P$2_2") (pintype "bidirectional"))
      (node (ref "X3") (pin "2") (pinfunction "2_2") (pintype "bidirectional"))
    )
    (net (code "63") (name "Net-(J2-P$2)") (class "Default")
      (node (ref "J2") (pin "2") (pinfunction "P$2_2") (pintype "bidirectional"))
      (node (ref "X3") (pin "3") (pinfunction "3_3") (pintype "bidirectional"))
    )
    (net (code "64") (name "Net-(LED2A-C)") (class "Default")
      (node (ref "LED2") (pin "C3") (pinfunction "C_C3") (pintype "passive"))
      (node (ref "R3") (pin "P$2") (pinfunction "2_P$2") (pintype "passive"))
    )
    (net (code "65") (name "Net-(LED2B-C)") (class "Default")
      (node (ref "LED2") (pin "C2") (pinfunction "C_C2") (pintype "passive"))
      (node (ref "R2") (pin "P$2") (pinfunction "2_P$2") (pintype "passive"))
    )
    (net (code "66") (name "Net-(LED2C-C)") (class "Default")
      (node (ref "LED2") (pin "C1") (pinfunction "C_C1") (pintype "passive"))
      (node (ref "R4") (pin "P$2") (pinfunction "2_P$2") (pintype "passive"))
    )
    (net (code "67") (name "Net-(R1-2)") (class "Default")
      (node (ref "LED1") (pin "C") (pinfunction "C_C") (pintype "passive"))
      (node (ref "R1") (pin "P$2") (pinfunction "2_P$2") (pintype "passive"))
    )
    (net (code "68") (name "Net-(R21-2)") (class "Default")
      (node (ref "R21") (pin "P$2") (pinfunction "2_P$2") (pintype "passive"))
      (node (ref "X2") (pin "2") (pinfunction "2_2") (pintype "bidirectional"))
    )
    (net (code "69") (name "Net-(R24-2)") (class "Default")
      (node (ref "R24") (pin "P$2") (pinfunction "2_P$2") (pintype "passive"))
      (node (ref "X2") (pin "3") (pinfunction "3_3") (pintype "bidirectional"))
    )
    (net (code "70") (name "unconnected-(IC2-PB4{slash}JNTRST-TIM3CH1{slash}SPI1MISO-Pad40)") (class "Default")
      (node (ref "IC2") (pin "40") (pinfunction "PB4/JNTRST-TIM3CH1/SPI1MISO_40") (pintype "bidirectional"))
    )
    (net (code "71") (name "unconnected-(IC2-PC15-OSC32_OUT-Pad4)") (class "Default")
      (node (ref "IC2") (pin "4") (pinfunction "PC15-OSC32_OUT_4") (pintype "bidirectional"))
    )
    (net (code "72") (name "unconnected-(IC2-PD1-OSC_OUT-Pad6)") (class "Default")
      (node (ref "IC2") (pin "6") (pinfunction "PD1-OSC_OUT_6") (pintype "output"))
    )
    (net (code "73") (name "unconnected-(IC3-VREF-Pad5)") (class "Default")
      (node (ref "IC3") (pin "5") (pinfunction "VREF_5") (pintype "output"))
    )
    (net (code "74") (name "unconnected-(Q1-TRI-Pad1)") (class "Default")
      (node (ref "Q1") (pin "1") (pinfunction "TRI_1") (pintype "output"))
    )
  )
)
